# main_board-v2_1.net
KiCad netlist of a schematic drawn in EAGLE
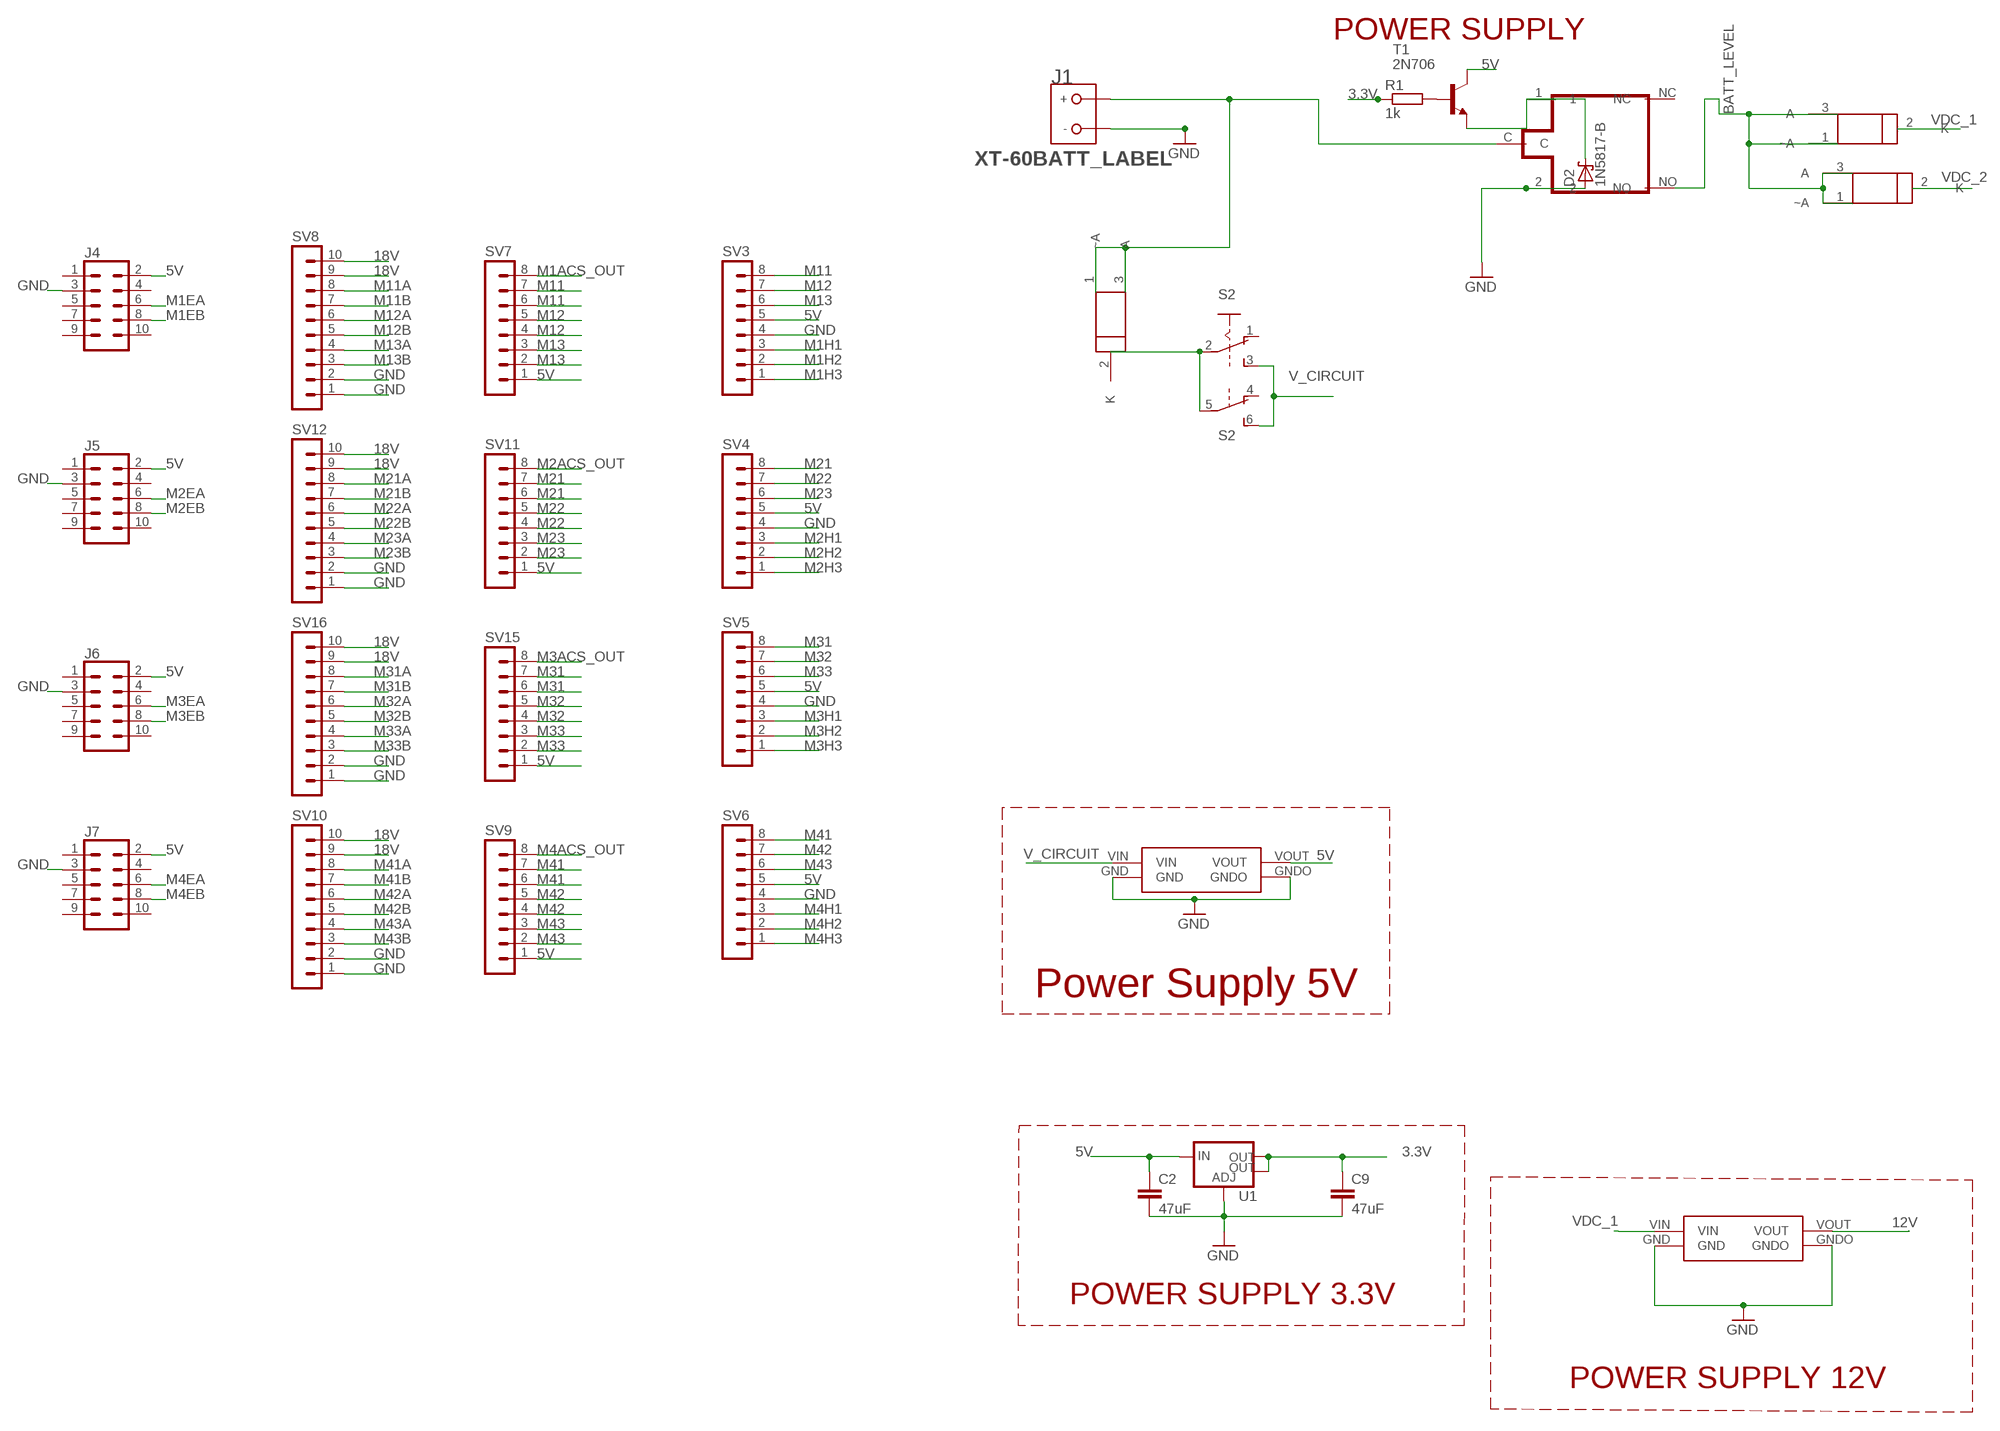
[diagram p0: schematic, sheet 1, part 1 of 2]
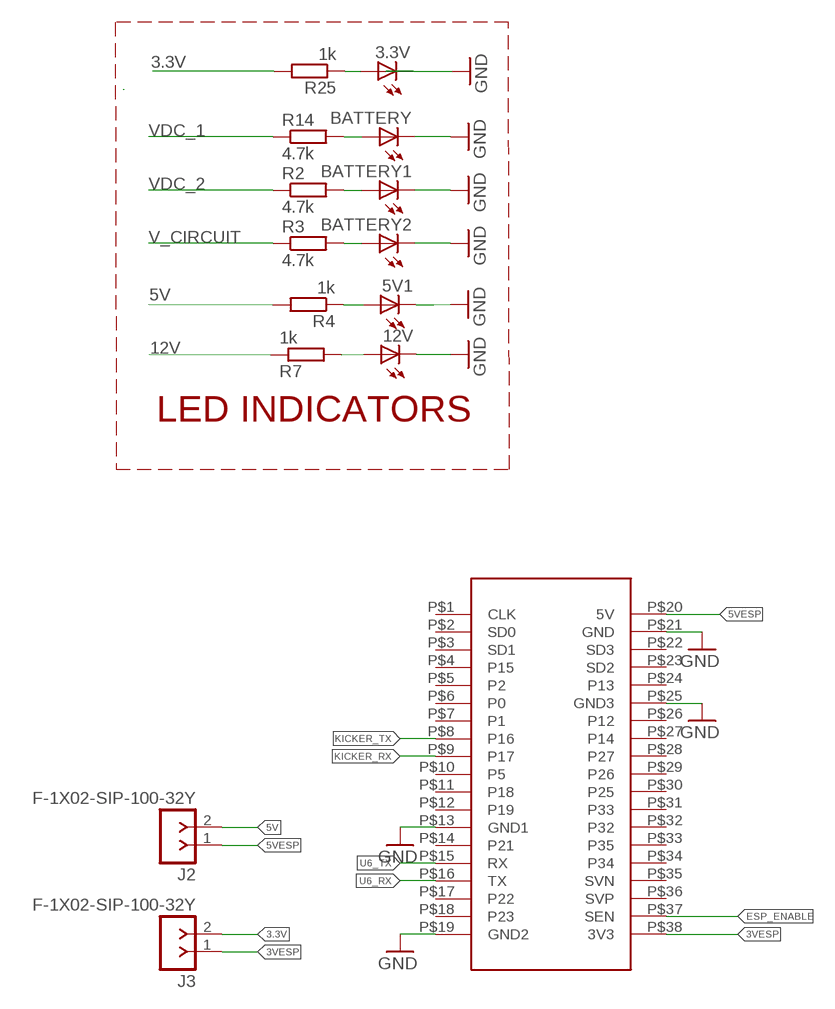
[diagram p1: schematic, sheet 1, part 2 of 2]

(export (version "E")
  (design (tool "Eeschema 10.0.6"))
  (components
    (comp (ref "3.3V")
      (value "LEDCHIPLED_0805")
      (footprint "eagle-import:CHIPLED_0805")
      (libsource (lib "eagle-import") (part "LEDCHIPLED_0805"))
    )
    (comp (ref "5V1")
      (value "LEDCHIPLED_0805")
      (footprint "eagle-import:CHIPLED_0805")
      (libsource (lib "eagle-import") (part "LEDCHIPLED_0805"))
    )
    (comp (ref "12V")
      (value "LEDCHIPLED_0805")
      (footprint "eagle-import:CHIPLED_0805")
      (libsource (lib "eagle-import") (part "LEDCHIPLED_0805"))
    )
    (comp (ref "BATTERY")
      (value "LEDCHIPLED_0805")
      (footprint "eagle-import:CHIPLED_0805")
      (libsource (lib "eagle-import") (part "LEDCHIPLED_0805"))
    )
    (comp (ref "BATTERY1")
      (value "LEDCHIPLED_0805")
      (footprint "eagle-import:CHIPLED_0805")
      (libsource (lib "eagle-import") (part "LEDCHIPLED_0805"))
    )
    (comp (ref "BATTERY2")
      (value "LEDCHIPLED_0805")
      (footprint "eagle-import:CHIPLED_0805")
      (libsource (lib "eagle-import") (part "LEDCHIPLED_0805"))
    )
    (comp (ref "C2")
      (value "47uF")
      (footprint "eagle-import:C1206")
      (libsource (lib "eagle-import") (part "C-EUC1206"))
    )
    (comp (ref "C9")
      (value "47uF")
      (footprint "eagle-import:C1206")
      (libsource (lib "eagle-import") (part "C-EUC1206"))
    )
    (comp (ref "D2")
      (value "1N5817-B")
      (footprint "eagle-import:DO41-7.6")
      (libsource (lib "eagle-import") (part "1N5817-B"))
    )
    (comp (ref "J1")
      (value "XT-60BATT_LABEL")
      (footprint "eagle-import:XT-60")
      (libsource (lib "eagle-import") (part "XT-60BATT_LABEL"))
    )
    (comp (ref "J2")
      (value "F-1X02-SIP-100-32Y")
      (footprint "eagle-import:SIP-100-02-32Y")
      (libsource (lib "eagle-import") (part "F-1X02-SIP-100-32Y"))
    )
    (comp (ref "J3")
      (value "F-1X02-SIP-100-32Y")
      (footprint "eagle-import:SIP-100-02-32Y")
      (libsource (lib "eagle-import") (part "F-1X02-SIP-100-32Y"))
    )
    (comp (ref "J4")
      (value "CONN_05X2SHD_LOCK")
      (footprint "eagle-import:2X5-SHROUDED_LOCK")
      (libsource (lib "eagle-import") (part "CONN_05X2SHD_LOCK"))
    )
    (comp (ref "J5")
      (value "CONN_05X2SHD_LOCK")
      (footprint "eagle-import:2X5-SHROUDED_LOCK")
      (libsource (lib "eagle-import") (part "CONN_05X2SHD_LOCK"))
    )
    (comp (ref "J6")
      (value "CONN_05X2SHD_LOCK")
      (footprint "eagle-import:2X5-SHROUDED_LOCK")
      (libsource (lib "eagle-import") (part "CONN_05X2SHD_LOCK"))
    )
    (comp (ref "J7")
      (value "CONN_05X2SHD_LOCK")
      (footprint "eagle-import:2X5-SHROUDED_LOCK")
      (libsource (lib "eagle-import") (part "CONN_05X2SHD_LOCK"))
    )
    (comp (ref "R1")
      (value "1k")
      (footprint "eagle-import:R1206")
      (libsource (lib "eagle-import") (part "R-EU_R1206"))
    )
    (comp (ref "R2")
      (value "4.7k")
      (footprint "eagle-import:R1206")
      (libsource (lib "eagle-import") (part "R-EU_R1206"))
    )
    (comp (ref "R3")
      (value "4.7k")
      (footprint "eagle-import:R1206")
      (libsource (lib "eagle-import") (part "R-EU_R1206"))
    )
    (comp (ref "R4")
      (value "1k")
      (footprint "eagle-import:R1206")
      (libsource (lib "eagle-import") (part "R-EU_R1206"))
    )
    (comp (ref "R7")
      (value "1k")
      (footprint "eagle-import:R1206")
      (libsource (lib "eagle-import") (part "R-EU_R1206"))
    )
    (comp (ref "R14")
      (value "4.7k")
      (footprint "eagle-import:R1206")
      (libsource (lib "eagle-import") (part "R-EU_R1206"))
    )
    (comp (ref "R25")
      (value "1k")
      (footprint "eagle-import:R1206")
      (libsource (lib "eagle-import") (part "R-EU_R1206"))
    )
    (comp (ref "S2")
      (value "A68-A31")
      (footprint "eagle-import:A68-A31")
      (libsource (lib "eagle-import") (part "A68-A31"))
    )
    (comp (ref "SV3")
      (value "MA08-1")
      (footprint "eagle-import:MA08-1")
      (libsource (lib "eagle-import") (part "MA08-1"))
    )
    (comp (ref "SV4")
      (value "MA08-1")
      (footprint "eagle-import:MA08-1")
      (libsource (lib "eagle-import") (part "MA08-1"))
    )
    (comp (ref "SV5")
      (value "MA08-1")
      (footprint "eagle-import:MA08-1")
      (libsource (lib "eagle-import") (part "MA08-1"))
    )
    (comp (ref "SV6")
      (value "MA08-1")
      (footprint "eagle-import:MA08-1")
      (libsource (lib "eagle-import") (part "MA08-1"))
    )
    (comp (ref "SV7")
      (value "MA08-1")
      (footprint "eagle-import:MA08-1")
      (libsource (lib "eagle-import") (part "MA08-1"))
    )
    (comp (ref "SV8")
      (value "MA10-1")
      (footprint "eagle-import:MA10-1")
      (libsource (lib "eagle-import") (part "MA10-1"))
    )
    (comp (ref "SV9")
      (value "MA08-1")
      (footprint "eagle-import:MA08-1")
      (libsource (lib "eagle-import") (part "MA08-1"))
    )
    (comp (ref "SV10")
      (value "MA10-1")
      (footprint "eagle-import:MA10-1")
      (libsource (lib "eagle-import") (part "MA10-1"))
    )
    (comp (ref "SV11")
      (value "MA08-1")
      (footprint "eagle-import:MA08-1")
      (libsource (lib "eagle-import") (part "MA08-1"))
    )
    (comp (ref "SV12")
      (value "MA10-1")
      (footprint "eagle-import:MA10-1")
      (libsource (lib "eagle-import") (part "MA10-1"))
    )
    (comp (ref "SV15")
      (value "MA08-1")
      (footprint "eagle-import:MA08-1")
      (libsource (lib "eagle-import") (part "MA08-1"))
    )
    (comp (ref "SV16")
      (value "MA10-1")
      (footprint "eagle-import:MA10-1")
      (libsource (lib "eagle-import") (part "MA10-1"))
    )
    (comp (ref "T1")
      (value "2N706")
      (footprint "eagle-import:TO18")
      (libsource (lib "eagle-import") (part "2N706"))
    )
    (comp (ref "U$2")
      (value "REL")
      (footprint "eagle-import:REL")
      (libsource (lib "eagle-import") (part "REL"))
    )
    (comp (ref "U$3")
      (value "BUCK")
      (footprint "eagle-import:BUCK")
      (libsource (lib "eagle-import") (part "BUCK"))
    )
    (comp (ref "U$4")
      (value "BUCK")
      (footprint "eagle-import:BUCK")
      (libsource (lib "eagle-import") (part "BUCK"))
    )
    (comp (ref "U$6")
      (value "NODEMCU32S")
      (footprint "eagle-import:NODEMCU32")
      (libsource (lib "eagle-import") (part "NODEMCU32S"))
    )
    (comp (ref "U1")
      (value "V_REG_LM1117SOT223")
      (footprint "eagle-import:SOT223")
      (libsource (lib "eagle-import") (part "V_REG_LM1117SOT223"))
    )
    (comp (ref "U2")
      (value "LP38690DT-3.3")
      (footprint "eagle-import:TO228P1042X238-3N")
      (libsource (lib "eagle-import") (part "LP38690DT-3.3"))
    )
    (comp (ref "U3")
      (value "LP38690DT-3.3")
      (footprint "eagle-import:TO228P1042X238-3N")
      (libsource (lib "eagle-import") (part "LP38690DT-3.3"))
    )
    (comp (ref "U4")
      (value "LP38690DT-3.3")
      (footprint "eagle-import:TO228P1042X238-3N")
      (libsource (lib "eagle-import") (part "LP38690DT-3.3"))
    )
  )
  (nets
    (net (code "1") (name "/12V") (class "Default")
      (node (ref "R7") (pin "1") (pinfunction "1_1") (pintype "passive"))
      (node (ref "U$4") (pin "VOUT") (pinfunction "VOUT_VOUT") (pintype "bidirectional"))
    )
    (net (code "2") (name "/18V") (class "Default")
      (node (ref "SV10") (pin "10") (pinfunction "10_10") (pintype "passive"))
      (node (ref "SV10") (pin "9") (pinfunction "9_9") (pintype "passive"))
      (node (ref "SV12") (pin "10") (pinfunction "10_10") (pintype "passive"))
      (node (ref "SV12") (pin "9") (pinfunction "9_9") (pintype "passive"))
      (node (ref "SV16") (pin "10") (pinfunction "10_10") (pintype "passive"))
      (node (ref "SV16") (pin "9") (pinfunction "9_9") (pintype "passive"))
      (node (ref "SV8") (pin "10") (pinfunction "10_10") (pintype "passive"))
      (node (ref "SV8") (pin "9") (pinfunction "9_9") (pintype "passive"))
    )
    (net (code "3") (name "/BATT_LEVEL") (class "Default")
      (node (ref "U$2") (pin "NO") (pinfunction "NO_NO") (pintype "bidirectional"))
      (node (ref "U2") (pin "1") (pinfunction "~{A}_1") (pintype "bidirectional"))
      (node (ref "U2") (pin "3") (pinfunction "A_3") (pintype "bidirectional"))
      (node (ref "U4") (pin "1") (pinfunction "~{A}_1") (pintype "bidirectional"))
      (node (ref "U4") (pin "3") (pinfunction "A_3") (pintype "bidirectional"))
    )
    (net (code "4") (name "/M1ACS_OUT") (class "Default")
      (node (ref "SV7") (pin "8") (pinfunction "8_8") (pintype "passive"))
    )
    (net (code "5") (name "/M1EA") (class "Default")
      (node (ref "J4") (pin "6") (pinfunction "6_6") (pintype "passive"))
    )
    (net (code "6") (name "/M1EB") (class "Default")
      (node (ref "J4") (pin "8") (pinfunction "8_8") (pintype "passive"))
    )
    (net (code "7") (name "/M1H1") (class "Default")
      (node (ref "SV3") (pin "3") (pinfunction "3_3") (pintype "passive"))
    )
    (net (code "8") (name "/M1H2") (class "Default")
      (node (ref "SV3") (pin "2") (pinfunction "2_2") (pintype "passive"))
    )
    (net (code "9") (name "/M1H3") (class "Default")
      (node (ref "SV3") (pin "1") (pinfunction "1_1") (pintype "passive"))
    )
    (net (code "10") (name "/M2ACS_OUT") (class "Default")
      (node (ref "SV11") (pin "8") (pinfunction "8_8") (pintype "passive"))
    )
    (net (code "11") (name "/M2EA") (class "Default")
      (node (ref "J5") (pin "6") (pinfunction "6_6") (pintype "passive"))
    )
    (net (code "12") (name "/M2EB") (class "Default")
      (node (ref "J5") (pin "8") (pinfunction "8_8") (pintype "passive"))
    )
    (net (code "13") (name "/M2H1") (class "Default")
      (node (ref "SV4") (pin "3") (pinfunction "3_3") (pintype "passive"))
    )
    (net (code "14") (name "/M2H2") (class "Default")
      (node (ref "SV4") (pin "2") (pinfunction "2_2") (pintype "passive"))
    )
    (net (code "15") (name "/M2H3") (class "Default")
      (node (ref "SV4") (pin "1") (pinfunction "1_1") (pintype "passive"))
    )
    (net (code "16") (name "/M3ACS_OUT") (class "Default")
      (node (ref "SV15") (pin "8") (pinfunction "8_8") (pintype "passive"))
    )
    (net (code "17") (name "/M3EA") (class "Default")
      (node (ref "J6") (pin "6") (pinfunction "6_6") (pintype "passive"))
    )
    (net (code "18") (name "/M3EB") (class "Default")
      (node (ref "J6") (pin "8") (pinfunction "8_8") (pintype "passive"))
    )
    (net (code "19") (name "/M3H1") (class "Default")
      (node (ref "SV5") (pin "3") (pinfunction "3_3") (pintype "passive"))
    )
    (net (code "20") (name "/M3H2") (class "Default")
      (node (ref "SV5") (pin "2") (pinfunction "2_2") (pintype "passive"))
    )
    (net (code "21") (name "/M3H3") (class "Default")
      (node (ref "SV5") (pin "1") (pinfunction "1_1") (pintype "passive"))
    )
    (net (code "22") (name "/M4ACS_OUT") (class "Default")
      (node (ref "SV9") (pin "8") (pinfunction "8_8") (pintype "passive"))
    )
    (net (code "23") (name "/M4EA") (class "Default")
      (node (ref "J7") (pin "6") (pinfunction "6_6") (pintype "passive"))
    )
    (net (code "24") (name "/M4EB") (class "Default")
      (node (ref "J7") (pin "8") (pinfunction "8_8") (pintype "passive"))
    )
    (net (code "25") (name "/M4H1") (class "Default")
      (node (ref "SV6") (pin "3") (pinfunction "3_3") (pintype "passive"))
    )
    (net (code "26") (name "/M4H2") (class "Default")
      (node (ref "SV6") (pin "2") (pinfunction "2_2") (pintype "passive"))
    )
    (net (code "27") (name "/M4H3") (class "Default")
      (node (ref "SV6") (pin "1") (pinfunction "1_1") (pintype "passive"))
    )
    (net (code "28") (name "/M11") (class "Default")
      (node (ref "SV3") (pin "8") (pinfunction "8_8") (pintype "passive"))
      (node (ref "SV7") (pin "6") (pinfunction "6_6") (pintype "passive"))
      (node (ref "SV7") (pin "7") (pinfunction "7_7") (pintype "passive"))
    )
    (net (code "29") (name "/M11A") (class "Default")
      (node (ref "SV8") (pin "8") (pinfunction "8_8") (pintype "passive"))
    )
    (net (code "30") (name "/M11B") (class "Default")
      (node (ref "SV8") (pin "7") (pinfunction "7_7") (pintype "passive"))
    )
    (net (code "31") (name "/M12") (class "Default")
      (node (ref "SV3") (pin "7") (pinfunction "7_7") (pintype "passive"))
      (node (ref "SV7") (pin "4") (pinfunction "4_4") (pintype "passive"))
      (node (ref "SV7") (pin "5") (pinfunction "5_5") (pintype "passive"))
    )
    (net (code "32") (name "/M12A") (class "Default")
      (node (ref "SV8") (pin "6") (pinfunction "6_6") (pintype "passive"))
    )
    (net (code "33") (name "/M12B") (class "Default")
      (node (ref "SV8") (pin "5") (pinfunction "5_5") (pintype "passive"))
    )
    (net (code "34") (name "/M13") (class "Default")
      (node (ref "SV3") (pin "6") (pinfunction "6_6") (pintype "passive"))
      (node (ref "SV7") (pin "2") (pinfunction "2_2") (pintype "passive"))
      (node (ref "SV7") (pin "3") (pinfunction "3_3") (pintype "passive"))
    )
    (net (code "35") (name "/M13A") (class "Default")
      (node (ref "SV8") (pin "4") (pinfunction "4_4") (pintype "passive"))
    )
    (net (code "36") (name "/M13B") (class "Default")
      (node (ref "SV8") (pin "3") (pinfunction "3_3") (pintype "passive"))
    )
    (net (code "37") (name "/M21") (class "Default")
      (node (ref "SV11") (pin "6") (pinfunction "6_6") (pintype "passive"))
      (node (ref "SV11") (pin "7") (pinfunction "7_7") (pintype "passive"))
      (node (ref "SV4") (pin "8") (pinfunction "8_8") (pintype "passive"))
    )
    (net (code "38") (name "/M21A") (class "Default")
      (node (ref "SV12") (pin "8") (pinfunction "8_8") (pintype "passive"))
    )
    (net (code "39") (name "/M21B") (class "Default")
      (node (ref "SV12") (pin "7") (pinfunction "7_7") (pintype "passive"))
    )
    (net (code "40") (name "/M22") (class "Default")
      (node (ref "SV11") (pin "4") (pinfunction "4_4") (pintype "passive"))
      (node (ref "SV11") (pin "5") (pinfunction "5_5") (pintype "passive"))
      (node (ref "SV4") (pin "7") (pinfunction "7_7") (pintype "passive"))
    )
    (net (code "41") (name "/M22A") (class "Default")
      (node (ref "SV12") (pin "6") (pinfunction "6_6") (pintype "passive"))
    )
    (net (code "42") (name "/M22B") (class "Default")
      (node (ref "SV12") (pin "5") (pinfunction "5_5") (pintype "passive"))
    )
    (net (code "43") (name "/M23") (class "Default")
      (node (ref "SV11") (pin "2") (pinfunction "2_2") (pintype "passive"))
      (node (ref "SV11") (pin "3") (pinfunction "3_3") (pintype "passive"))
      (node (ref "SV4") (pin "6") (pinfunction "6_6") (pintype "passive"))
    )
    (net (code "44") (name "/M23A") (class "Default")
      (node (ref "SV12") (pin "4") (pinfunction "4_4") (pintype "passive"))
    )
    (net (code "45") (name "/M23B") (class "Default")
      (node (ref "SV12") (pin "3") (pinfunction "3_3") (pintype "passive"))
    )
    (net (code "46") (name "/M31") (class "Default")
      (node (ref "SV15") (pin "6") (pinfunction "6_6") (pintype "passive"))
      (node (ref "SV15") (pin "7") (pinfunction "7_7") (pintype "passive"))
      (node (ref "SV5") (pin "8") (pinfunction "8_8") (pintype "passive"))
    )
    (net (code "47") (name "/M31A") (class "Default")
      (node (ref "SV16") (pin "8") (pinfunction "8_8") (pintype "passive"))
    )
    (net (code "48") (name "/M31B") (class "Default")
      (node (ref "SV16") (pin "7") (pinfunction "7_7") (pintype "passive"))
    )
    (net (code "49") (name "/M32") (class "Default")
      (node (ref "SV15") (pin "4") (pinfunction "4_4") (pintype "passive"))
      (node (ref "SV15") (pin "5") (pinfunction "5_5") (pintype "passive"))
      (node (ref "SV5") (pin "7") (pinfunction "7_7") (pintype "passive"))
    )
    (net (code "50") (name "/M32A") (class "Default")
      (node (ref "SV16") (pin "6") (pinfunction "6_6") (pintype "passive"))
    )
    (net (code "51") (name "/M32B") (class "Default")
      (node (ref "SV16") (pin "5") (pinfunction "5_5") (pintype "passive"))
    )
    (net (code "52") (name "/M33") (class "Default")
      (node (ref "SV15") (pin "2") (pinfunction "2_2") (pintype "passive"))
      (node (ref "SV15") (pin "3") (pinfunction "3_3") (pintype "passive"))
      (node (ref "SV5") (pin "6") (pinfunction "6_6") (pintype "passive"))
    )
    (net (code "53") (name "/M33A") (class "Default")
      (node (ref "SV16") (pin "4") (pinfunction "4_4") (pintype "passive"))
    )
    (net (code "54") (name "/M33B") (class "Default")
      (node (ref "SV16") (pin "3") (pinfunction "3_3") (pintype "passive"))
    )
    (net (code "55") (name "/M41") (class "Default")
      (node (ref "SV6") (pin "8") (pinfunction "8_8") (pintype "passive"))
      (node (ref "SV9") (pin "6") (pinfunction "6_6") (pintype "passive"))
      (node (ref "SV9") (pin "7") (pinfunction "7_7") (pintype "passive"))
    )
    (net (code "56") (name "/M41A") (class "Default")
      (node (ref "SV10") (pin "8") (pinfunction "8_8") (pintype "passive"))
    )
    (net (code "57") (name "/M41B") (class "Default")
      (node (ref "SV10") (pin "7") (pinfunction "7_7") (pintype "passive"))
    )
    (net (code "58") (name "/M42") (class "Default")
      (node (ref "SV6") (pin "7") (pinfunction "7_7") (pintype "passive"))
      (node (ref "SV9") (pin "4") (pinfunction "4_4") (pintype "passive"))
      (node (ref "SV9") (pin "5") (pinfunction "5_5") (pintype "passive"))
    )
    (net (code "59") (name "/M42A") (class "Default")
      (node (ref "SV10") (pin "6") (pinfunction "6_6") (pintype "passive"))
    )
    (net (code "60") (name "/M42B") (class "Default")
      (node (ref "SV10") (pin "5") (pinfunction "5_5") (pintype "passive"))
    )
    (net (code "61") (name "/M43") (class "Default")
      (node (ref "SV6") (pin "6") (pinfunction "6_6") (pintype "passive"))
      (node (ref "SV9") (pin "2") (pinfunction "2_2") (pintype "passive"))
      (node (ref "SV9") (pin "3") (pinfunction "3_3") (pintype "passive"))
    )
    (net (code "62") (name "/M43A") (class "Default")
      (node (ref "SV10") (pin "4") (pinfunction "4_4") (pintype "passive"))
    )
    (net (code "63") (name "/M43B") (class "Default")
      (node (ref "SV10") (pin "3") (pinfunction "3_3") (pintype "passive"))
    )
    (net (code "64") (name "/VDC_1") (class "Default")
      (node (ref "R14") (pin "1") (pinfunction "1_1") (pintype "passive"))
      (node (ref "U$4") (pin "VIN") (pinfunction "VIN_VIN") (pintype "bidirectional"))
      (node (ref "U4") (pin "2") (pinfunction "K_2") (pintype "bidirectional"))
    )
    (net (code "65") (name "/VDC_2") (class "Default")
      (node (ref "R2") (pin "1") (pinfunction "1_1") (pintype "passive"))
      (node (ref "U2") (pin "2") (pinfunction "K_2") (pintype "bidirectional"))
    )
    (net (code "66") (name "/V_CIRCUIT") (class "Default")
      (node (ref "R3") (pin "1") (pinfunction "1_1") (pintype "passive"))
      (node (ref "S2") (pin "3") (pinfunction "S_3") (pintype "passive"))
      (node (ref "S2") (pin "6") (pinfunction "S_6") (pintype "passive"))
      (node (ref "U$3") (pin "VIN") (pinfunction "VIN_VIN") (pintype "bidirectional"))
    )
    (net (code "67") (name "3.3V") (class "Default")
      (node (ref "C9") (pin "1") (pinfunction "1_1") (pintype "passive"))
      (node (ref "J3") (pin "2") (pinfunction "2_2") (pintype "passive"))
      (node (ref "R1") (pin "1") (pinfunction "1_1") (pintype "passive"))
      (node (ref "R25") (pin "2") (pinfunction "2_2") (pintype "passive"))
      (node (ref "U1") (pin "2") (pinfunction "OUT_2") (pintype "output"))
      (node (ref "U1") (pin "4") (pinfunction "OUT_4") (pintype "output"))
    )
    (net (code "68") (name "3VESP") (class "Default")
      (node (ref "J3") (pin "1") (pinfunction "1_1") (pintype "passive"))
      (node (ref "U$6") (pin "P$38") (pinfunction "3V3_P$38") (pintype "bidirectional"))
    )
    (net (code "69") (name "5V") (class "Default")
      (node (ref "C2") (pin "1") (pinfunction "1_1") (pintype "passive"))
      (node (ref "J2") (pin "2") (pinfunction "2_2") (pintype "passive"))
      (node (ref "J4") (pin "2") (pinfunction "2_2") (pintype "passive"))
      (node (ref "J5") (pin "2") (pinfunction "2_2") (pintype "passive"))
      (node (ref "J6") (pin "2") (pinfunction "2_2") (pintype "passive"))
      (node (ref "J7") (pin "2") (pinfunction "2_2") (pintype "passive"))
      (node (ref "R4") (pin "2") (pinfunction "2_2") (pintype "passive"))
      (node (ref "SV11") (pin "1") (pinfunction "1_1") (pintype "passive"))
      (node (ref "SV15") (pin "1") (pinfunction "1_1") (pintype "passive"))
      (node (ref "SV3") (pin "5") (pinfunction "5_5") (pintype "passive"))
      (node (ref "SV4") (pin "5") (pinfunction "5_5") (pintype "passive"))
      (node (ref "SV5") (pin "5") (pinfunction "5_5") (pintype "passive"))
      (node (ref "SV6") (pin "5") (pinfunction "5_5") (pintype "passive"))
      (node (ref "SV7") (pin "1") (pinfunction "1_1") (pintype "passive"))
      (node (ref "SV9") (pin "1") (pinfunction "1_1") (pintype "passive"))
      (node (ref "T1") (pin "3") (pinfunction "C_3") (pintype "passive"))
      (node (ref "U$3") (pin "VOUT") (pinfunction "VOUT_VOUT") (pintype "bidirectional"))
      (node (ref "U1") (pin "3") (pinfunction "IN_3") (pintype "input"))
    )
    (net (code "70") (name "5VESP") (class "Default")
      (node (ref "J2") (pin "1") (pinfunction "1_1") (pintype "passive"))
      (node (ref "U$6") (pin "P$20") (pinfunction "5V_P$20") (pintype "bidirectional"))
    )
    (net (code "71") (name "ESP_ENABLE") (class "Default")
      (node (ref "U$6") (pin "P$37") (pinfunction "SEN_P$37") (pintype "bidirectional"))
    )
    (net (code "72") (name "GND") (class "Default")
      (node (ref "12V") (pin "C") (pinfunction "C_C") (pintype "passive"))
      (node (ref "3.3V") (pin "C") (pinfunction "C_C") (pintype "passive"))
      (node (ref "5V1") (pin "C") (pinfunction "C_C") (pintype "passive"))
      (node (ref "BATTERY") (pin "C") (pinfunction "C_C") (pintype "passive"))
      (node (ref "BATTERY1") (pin "C") (pinfunction "C_C") (pintype "passive"))
      (node (ref "BATTERY2") (pin "C") (pinfunction "C_C") (pintype "passive"))
      (node (ref "C2") (pin "2") (pinfunction "2_2") (pintype "passive"))
      (node (ref "C9") (pin "2") (pinfunction "2_2") (pintype "passive"))
      (node (ref "D2") (pin "A") (pinfunction "A_A") (pintype "passive"))
      (node (ref "J1") (pin "GND") (pinfunction "-_GND") (pintype "passive"))
      (node (ref "J4") (pin "3") (pinfunction "3_3") (pintype "passive"))
      (node (ref "J5") (pin "3") (pinfunction "3_3") (pintype "passive"))
      (node (ref "J6") (pin "3") (pinfunction "3_3") (pintype "passive"))
      (node (ref "J7") (pin "3") (pinfunction "3_3") (pintype "passive"))
      (node (ref "SV10") (pin "1") (pinfunction "1_1") (pintype "passive"))
      (node (ref "SV10") (pin "2") (pinfunction "2_2") (pintype "passive"))
      (node (ref "SV12") (pin "1") (pinfunction "1_1") (pintype "passive"))
      (node (ref "SV12") (pin "2") (pinfunction "2_2") (pintype "passive"))
      (node (ref "SV16") (pin "1") (pinfunction "1_1") (pintype "passive"))
      (node (ref "SV16") (pin "2") (pinfunction "2_2") (pintype "passive"))
      (node (ref "SV3") (pin "4") (pinfunction "4_4") (pintype "passive"))
      (node (ref "SV4") (pin "4") (pinfunction "4_4") (pintype "passive"))
      (node (ref "SV5") (pin "4") (pinfunction "4_4") (pintype "passive"))
      (node (ref "SV6") (pin "4") (pinfunction "4_4") (pintype "passive"))
      (node (ref "SV8") (pin "1") (pinfunction "1_1") (pintype "passive"))
      (node (ref "SV8") (pin "2") (pinfunction "2_2") (pintype "passive"))
      (node (ref "U$2") (pin "2") (pinfunction "2_2") (pintype "bidirectional"))
      (node (ref "U$3") (pin "GND") (pinfunction "GND_GND") (pintype "bidirectional"))
      (node (ref "U$3") (pin "GNDO") (pinfunction "GNDO_GNDO") (pintype "bidirectional"))
      (node (ref "U$4") (pin "GND") (pinfunction "GND_GND") (pintype "bidirectional"))
      (node (ref "U$4") (pin "GNDO") (pinfunction "GNDO_GNDO") (pintype "bidirectional"))
      (node (ref "U$6") (pin "P$13") (pinfunction "GND1_P$13") (pintype "bidirectional"))
      (node (ref "U$6") (pin "P$19") (pinfunction "GND2_P$19") (pintype "bidirectional"))
      (node (ref "U$6") (pin "P$21") (pinfunction "GND_P$21") (pintype "bidirectional"))
      (node (ref "U$6") (pin "P$25") (pinfunction "GND3_P$25") (pintype "bidirectional"))
      (node (ref "U1") (pin "1") (pinfunction "ADJ_1") (pintype "input"))
    )
    (net (code "73") (name "KICKER_RX") (class "Default")
      (node (ref "U$6") (pin "P$9") (pinfunction "P17_P$9") (pintype "bidirectional"))
    )
    (net (code "74") (name "KICKER_TX") (class "Default")
      (node (ref "U$6") (pin "P$8") (pinfunction "P16_P$8") (pintype "bidirectional"))
    )
    (net (code "75") (name "Net-(3.3V-PadA)") (class "Default")
      (node (ref "3.3V") (pin "A") (pinfunction "A_A") (pintype "passive"))
      (node (ref "R25") (pin "1") (pinfunction "1_1") (pintype "passive"))
    )
    (net (code "76") (name "Net-(5V1-PadA)") (class "Default")
      (node (ref "5V1") (pin "A") (pinfunction "A_A") (pintype "passive"))
      (node (ref "R4") (pin "1") (pinfunction "1_1") (pintype "passive"))
    )
    (net (code "77") (name "Net-(12V-PadA)") (class "Default")
      (node (ref "12V") (pin "A") (pinfunction "A_A") (pintype "passive"))
      (node (ref "R7") (pin "2") (pinfunction "2_2") (pintype "passive"))
    )
    (net (code "78") (name "Net-(BATTERY-PadA)") (class "Default")
      (node (ref "BATTERY") (pin "A") (pinfunction "A_A") (pintype "passive"))
      (node (ref "R14") (pin "2") (pinfunction "2_2") (pintype "passive"))
    )
    (net (code "79") (name "Net-(BATTERY1-PadA)") (class "Default")
      (node (ref "BATTERY1") (pin "A") (pinfunction "A_A") (pintype "passive"))
      (node (ref "R2") (pin "2") (pinfunction "2_2") (pintype "passive"))
    )
    (net (code "80") (name "Net-(BATTERY2-PadA)") (class "Default")
      (node (ref "BATTERY2") (pin "A") (pinfunction "A_A") (pintype "passive"))
      (node (ref "R3") (pin "2") (pinfunction "2_2") (pintype "passive"))
    )
    (net (code "81") (name "Net-(J1-+)") (class "Default")
      (node (ref "J1") (pin "BATT") (pinfunction "+_BATT") (pintype "passive"))
      (node (ref "U$2") (pin "C") (pinfunction "C_C") (pintype "bidirectional"))
      (node (ref "U3") (pin "1") (pinfunction "~{A}_1") (pintype "bidirectional"))
      (node (ref "U3") (pin "3") (pinfunction "A_3") (pintype "bidirectional"))
    )
    (net (code "82") (name "Net-(S2A-P)") (class "Default")
      (node (ref "S2") (pin "2") (pinfunction "P_2") (pintype "passive"))
      (node (ref "S2") (pin "5") (pinfunction "P_5") (pintype "passive"))
      (node (ref "U3") (pin "2") (pinfunction "K_2") (pintype "bidirectional"))
    )
    (net (code "83") (name "Net-(T1-B)") (class "Default")
      (node (ref "R1") (pin "2") (pinfunction "2_2") (pintype "passive"))
      (node (ref "T1") (pin "2") (pinfunction "B_2") (pintype "passive"))
    )
    (net (code "84") (name "Net-(T1-E)") (class "Default")
      (node (ref "D2") (pin "C") (pinfunction "C_C") (pintype "passive"))
      (node (ref "T1") (pin "1") (pinfunction "E_1") (pintype "passive"))
      (node (ref "U$2") (pin "1") (pinfunction "1_1") (pintype "bidirectional"))
    )
    (net (code "85") (name "U6_RX") (class "Default")
      (node (ref "U$6") (pin "P$16") (pinfunction "TX_P$16") (pintype "bidirectional"))
    )
    (net (code "86") (name "U6_TX") (class "Default")
      (node (ref "U$6") (pin "P$15") (pinfunction "RX_P$15") (pintype "bidirectional"))
    )
    (net (code "87") (name "unconnected-(J4-Pad1)") (class "Default")
      (node (ref "J4") (pin "1") (pinfunction "1_1") (pintype "passive"))
    )
    (net (code "88") (name "unconnected-(J4-Pad4)") (class "Default")
      (node (ref "J4") (pin "4") (pinfunction "4_4") (pintype "passive"))
    )
    (net (code "89") (name "unconnected-(J4-Pad5)") (class "Default")
      (node (ref "J4") (pin "5") (pinfunction "5_5") (pintype "passive"))
    )
    (net (code "90") (name "unconnected-(J4-Pad7)") (class "Default")
      (node (ref "J4") (pin "7") (pinfunction "7_7") (pintype "passive"))
    )
    (net (code "91") (name "unconnected-(J4-Pad9)") (class "Default")
      (node (ref "J4") (pin "9") (pinfunction "9_9") (pintype "passive"))
    )
    (net (code "92") (name "unconnected-(J4-Pad10)") (class "Default")
      (node (ref "J4") (pin "10") (pinfunction "10_10") (pintype "passive"))
    )
    (net (code "93") (name "unconnected-(J5-Pad1)") (class "Default")
      (node (ref "J5") (pin "1") (pinfunction "1_1") (pintype "passive"))
    )
    (net (code "94") (name "unconnected-(J5-Pad4)") (class "Default")
      (node (ref "J5") (pin "4") (pinfunction "4_4") (pintype "passive"))
    )
    (net (code "95") (name "unconnected-(J5-Pad5)") (class "Default")
      (node (ref "J5") (pin "5") (pinfunction "5_5") (pintype "passive"))
    )
    (net (code "96") (name "unconnected-(J5-Pad7)") (class "Default")
      (node (ref "J5") (pin "7") (pinfunction "7_7") (pintype "passive"))
    )
    (net (code "97") (name "unconnected-(J5-Pad9)") (class "Default")
      (node (ref "J5") (pin "9") (pinfunction "9_9") (pintype "passive"))
    )
    (net (code "98") (name "unconnected-(J5-Pad10)") (class "Default")
      (node (ref "J5") (pin "10") (pinfunction "10_10") (pintype "passive"))
    )
    (net (code "99") (name "unconnected-(J6-Pad1)") (class "Default")
      (node (ref "J6") (pin "1") (pinfunction "1_1") (pintype "passive"))
    )
    (net (code "100") (name "unconnected-(J6-Pad4)") (class "Default")
      (node (ref "J6") (pin "4") (pinfunction "4_4") (pintype "passive"))
    )
    (net (code "101") (name "unconnected-(J6-Pad5)") (class "Default")
      (node (ref "J6") (pin "5") (pinfunction "5_5") (pintype "passive"))
    )
    (net (code "102") (name "unconnected-(J6-Pad7)") (class "Default")
      (node (ref "J6") (pin "7") (pinfunction "7_7") (pintype "passive"))
    )
    (net (code "103") (name "unconnected-(J6-Pad9)") (class "Default")
      (node (ref "J6") (pin "9") (pinfunction "9_9") (pintype "passive"))
    )
    (net (code "104") (name "unconnected-(J6-Pad10)") (class "Default")
      (node (ref "J6") (pin "10") (pinfunction "10_10") (pintype "passive"))
    )
    (net (code "105") (name "unconnected-(J7-Pad1)") (class "Default")
      (node (ref "J7") (pin "1") (pinfunction "1_1") (pintype "passive"))
    )
    (net (code "106") (name "unconnected-(J7-Pad4)") (class "Default")
      (node (ref "J7") (pin "4") (pinfunction "4_4") (pintype "passive"))
    )
    (net (code "107") (name "unconnected-(J7-Pad5)") (class "Default")
      (node (ref "J7") (pin "5") (pinfunction "5_5") (pintype "passive"))
    )
    (net (code "108") (name "unconnected-(J7-Pad7)") (class "Default")
      (node (ref "J7") (pin "7") (pinfunction "7_7") (pintype "passive"))
    )
    (net (code "109") (name "unconnected-(J7-Pad9)") (class "Default")
      (node (ref "J7") (pin "9") (pinfunction "9_9") (pintype "passive"))
    )
    (net (code "110") (name "unconnected-(J7-Pad10)") (class "Default")
      (node (ref "J7") (pin "10") (pinfunction "10_10") (pintype "passive"))
    )
    (net (code "111") (name "unconnected-(S2A-O-Pad1)") (class "Default")
      (node (ref "S2") (pin "1") (pinfunction "O_1") (pintype "passive"))
    )
    (net (code "112") (name "unconnected-(S2B-O-Pad4)") (class "Default")
      (node (ref "S2") (pin "4") (pinfunction "O_4") (pintype "passive"))
    )
    (net (code "113") (name "unconnected-(U$2-PadNC)") (class "Default")
      (node (ref "U$2") (pin "NC") (pinfunction "NC_NC") (pintype "bidirectional"))
    )
    (net (code "114") (name "unconnected-(U$6-CLK-PadP$1)") (class "Default")
      (node (ref "U$6") (pin "P$1") (pinfunction "CLK_P$1") (pintype "bidirectional"))
    )
    (net (code "115") (name "unconnected-(U$6-P0-PadP$6)") (class "Default")
      (node (ref "U$6") (pin "P$6") (pinfunction "P0_P$6") (pintype "bidirectional"))
    )
    (net (code "116") (name "unconnected-(U$6-P1-PadP$7)") (class "Default")
      (node (ref "U$6") (pin "P$7") (pinfunction "P1_P$7") (pintype "bidirectional"))
    )
    (net (code "117") (name "unconnected-(U$6-P2-PadP$5)") (class "Default")
      (node (ref "U$6") (pin "P$5") (pinfunction "P2_P$5") (pintype "bidirectional"))
    )
    (net (code "118") (name "unconnected-(U$6-P5-PadP$10)") (class "Default")
      (node (ref "U$6") (pin "P$10") (pinfunction "P5_P$10") (pintype "bidirectional"))
    )
    (net (code "119") (name "unconnected-(U$6-P12-PadP$26)") (class "Default")
      (node (ref "U$6") (pin "P$26") (pinfunction "P12_P$26") (pintype "bidirectional"))
    )
    (net (code "120") (name "unconnected-(U$6-P13-PadP$24)") (class "Default")
      (node (ref "U$6") (pin "P$24") (pinfunction "P13_P$24") (pintype "bidirectional"))
    )
    (net (code "121") (name "unconnected-(U$6-P14-PadP$27)") (class "Default")
      (node (ref "U$6") (pin "P$27") (pinfunction "P14_P$27") (pintype "bidirectional"))
    )
    (net (code "122") (name "unconnected-(U$6-P15-PadP$4)") (class "Default")
      (node (ref "U$6") (pin "P$4") (pinfunction "P15_P$4") (pintype "bidirectional"))
    )
    (net (code "123") (name "unconnected-(U$6-P18-PadP$11)") (class "Default")
      (node (ref "U$6") (pin "P$11") (pinfunction "P18_P$11") (pintype "bidirectional"))
    )
    (net (code "124") (name "unconnected-(U$6-P19-PadP$12)") (class "Default")
      (node (ref "U$6") (pin "P$12") (pinfunction "P19_P$12") (pintype "bidirectional"))
    )
    (net (code "125") (name "unconnected-(U$6-P21-PadP$14)") (class "Default")
      (node (ref "U$6") (pin "P$14") (pinfunction "P21_P$14") (pintype "bidirectional"))
    )
    (net (code "126") (name "unconnected-(U$6-P22-PadP$17)") (class "Default")
      (node (ref "U$6") (pin "P$17") (pinfunction "P22_P$17") (pintype "bidirectional"))
    )
    (net (code "127") (name "unconnected-(U$6-P23-PadP$18)") (class "Default")
      (node (ref "U$6") (pin "P$18") (pinfunction "P23_P$18") (pintype "bidirectional"))
    )
    (net (code "128") (name "unconnected-(U$6-P25-PadP$30)") (class "Default")
      (node (ref "U$6") (pin "P$30") (pinfunction "P25_P$30") (pintype "bidirectional"))
    )
    (net (code "129") (name "unconnected-(U$6-P26-PadP$29)") (class "Default")
      (node (ref "U$6") (pin "P$29") (pinfunction "P26_P$29") (pintype "bidirectional"))
    )
    (net (code "130") (name "unconnected-(U$6-P27-PadP$28)") (class "Default")
      (node (ref "U$6") (pin "P$28") (pinfunction "P27_P$28") (pintype "bidirectional"))
    )
    (net (code "131") (name "unconnected-(U$6-P32-PadP$32)") (class "Default")
      (node (ref "U$6") (pin "P$32") (pinfunction "P32_P$32") (pintype "bidirectional"))
    )
    (net (code "132") (name "unconnected-(U$6-P33-PadP$31)") (class "Default")
      (node (ref "U$6") (pin "P$31") (pinfunction "P33_P$31") (pintype "bidirectional"))
    )
    (net (code "133") (name "unconnected-(U$6-P34-PadP$34)") (class "Default")
      (node (ref "U$6") (pin "P$34") (pinfunction "P34_P$34") (pintype "bidirectional"))
    )
    (net (code "134") (name "unconnected-(U$6-P35-PadP$33)") (class "Default")
      (node (ref "U$6") (pin "P$33") (pinfunction "P35_P$33") (pintype "bidirectional"))
    )
    (net (code "135") (name "unconnected-(U$6-SD0-PadP$2)") (class "Default")
      (node (ref "U$6") (pin "P$2") (pinfunction "SD0_P$2") (pintype "bidirectional"))
    )
    (net (code "136") (name "unconnected-(U$6-SD1-PadP$3)") (class "Default")
      (node (ref "U$6") (pin "P$3") (pinfunction "SD1_P$3") (pintype "bidirectional"))
    )
    (net (code "137") (name "unconnected-(U$6-SD2-PadP$23)") (class "Default")
      (node (ref "U$6") (pin "P$23") (pinfunction "SD2_P$23") (pintype "bidirectional"))
    )
    (net (code "138") (name "unconnected-(U$6-SD3-PadP$22)") (class "Default")
      (node (ref "U$6") (pin "P$22") (pinfunction "SD3_P$22") (pintype "bidirectional"))
    )
    (net (code "139") (name "unconnected-(U$6-SVN-PadP$35)") (class "Default")
      (node (ref "U$6") (pin "P$35") (pinfunction "SVN_P$35") (pintype "bidirectional"))
    )
    (net (code "140") (name "unconnected-(U$6-SVP-PadP$36)") (class "Default")
      (node (ref "U$6") (pin "P$36") (pinfunction "SVP_P$36") (pintype "bidirectional"))
    )
  )
)
